# Crystal_Cmoy_Sch_EaglePCB_4.net
KiCad netlist of a schematic drawn in EAGLE
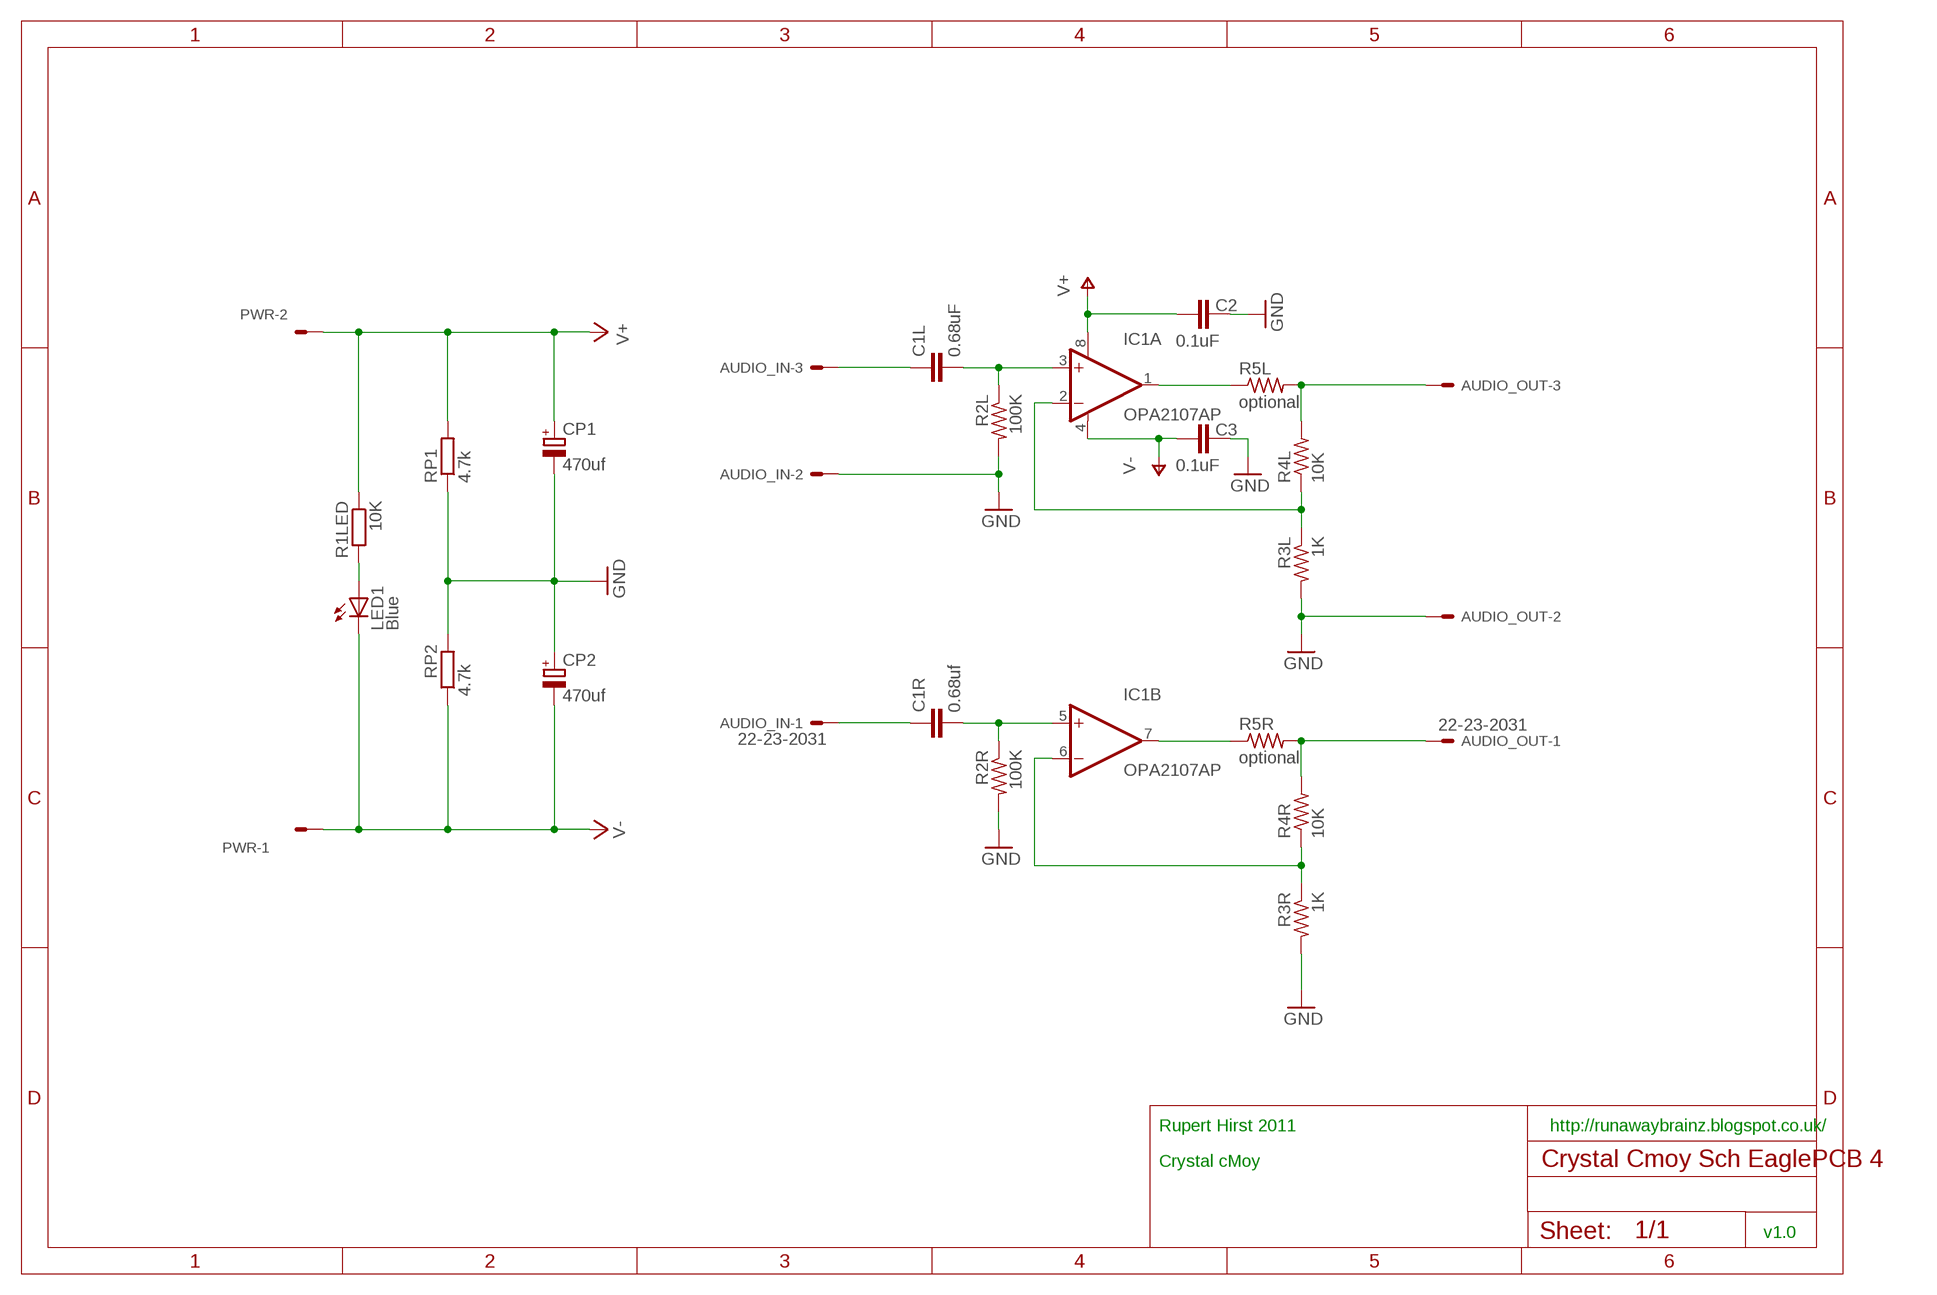
[diagram p0: schematic, sheet 1]

(export (version "E")
  (design (tool "Eeschema 10.0.6"))
  (components
    (comp (ref "AUDIO_IN")
      (value "22-23-2031")
      (footprint "eagle-import:22-23-2031")
      (libsource (lib "eagle-import") (part "22-23-2031"))
    )
    (comp (ref "AUDIO_OUT")
      (value "22-23-2031")
      (footprint "eagle-import:22-23-2031")
      (libsource (lib "eagle-import") (part "22-23-2031"))
    )
    (comp (ref "C1L")
      (value "0.68uF")
      (footprint "eagle-import:C15B7")
      (libsource (lib "eagle-import") (part "C15/7"))
    )
    (comp (ref "C1R")
      (value "0.68uf")
      (footprint "eagle-import:C15B7")
      (libsource (lib "eagle-import") (part "C15/7"))
    )
    (comp (ref "C2")
      (value "0.1uF")
      (footprint "eagle-import:C5B2.5")
      (libsource (lib "eagle-import") (part "C5/2.5"))
    )
    (comp (ref "C3")
      (value "0.1uF")
      (footprint "eagle-import:C5B5.5")
      (libsource (lib "eagle-import") (part "C5/5.5"))
    )
    (comp (ref "CP1")
      (value "470uf")
      (footprint "eagle-import:E5-13")
      (libsource (lib "eagle-import") (part "CPOL-EUE5-13"))
    )
    (comp (ref "CP2")
      (value "470uf")
      (footprint "eagle-import:E5-13")
      (libsource (lib "eagle-import") (part "CPOL-EUE5-13"))
    )
    (comp (ref "IC1")
      (value "OPA2107AP")
      (footprint "eagle-import:DIL08")
      (libsource (lib "eagle-import") (part "OPA2132P"))
    )
    (comp (ref "LED1")
      (value "Blue")
      (footprint "eagle-import:LED3MM")
      (libsource (lib "eagle-import") (part "LED3MM"))
    )
    (comp (ref "PWR")
      (value "22-23-2021")
      (footprint "eagle-import:22-23-2021")
      (libsource (lib "eagle-import") (part "22-23-2021"))
    )
    (comp (ref "R1LED")
      (value "10K")
      (footprint "eagle-import:0207_2V")
      (libsource (lib "eagle-import") (part "R-EU_0207/2V"))
    )
    (comp (ref "R2L")
      (value "100K")
      (footprint "eagle-import:0207_10")
      (libsource (lib "eagle-import") (part "R-US_0207/10"))
    )
    (comp (ref "R2R")
      (value "100K")
      (footprint "eagle-import:0207_10")
      (libsource (lib "eagle-import") (part "R-US_0207/10"))
    )
    (comp (ref "R3L")
      (value "1K")
      (footprint "eagle-import:0207_10")
      (libsource (lib "eagle-import") (part "R-US_0207/10"))
    )
    (comp (ref "R3R")
      (value "1K")
      (footprint "eagle-import:0207_10")
      (libsource (lib "eagle-import") (part "R-US_0207/10"))
    )
    (comp (ref "R4L")
      (value "10K")
      (footprint "eagle-import:0207_10")
      (libsource (lib "eagle-import") (part "R-US_0207/10"))
    )
    (comp (ref "R4R")
      (value "10K")
      (footprint "eagle-import:0207_10")
      (libsource (lib "eagle-import") (part "R-US_0207/10"))
    )
    (comp (ref "R5L")
      (value "optional")
      (footprint "eagle-import:0207_10")
      (libsource (lib "eagle-import") (part "R-US_0207/10"))
    )
    (comp (ref "R5R")
      (value "optional")
      (footprint "eagle-import:0207_10")
      (libsource (lib "eagle-import") (part "R-US_0207/10"))
    )
    (comp (ref "RP1")
      (value "4.7k")
      (footprint "eagle-import:0207_10")
      (libsource (lib "eagle-import") (part "R-EU_0207/10"))
    )
    (comp (ref "RP2")
      (value "4.7k")
      (footprint "eagle-import:0207_10")
      (libsource (lib "eagle-import") (part "R-EU_0207/10"))
    )
  )
  (nets
    (net (code "1") (name "GND") (class "Default")
      (node (ref "AUDIO_IN") (pin "2") (pinfunction "S_2") (pintype "passive"))
      (node (ref "AUDIO_OUT") (pin "2") (pinfunction "S_2") (pintype "passive"))
      (node (ref "C2") (pin "1") (pinfunction "1_1") (pintype "passive"))
      (node (ref "C3") (pin "2") (pinfunction "2_2") (pintype "passive"))
      (node (ref "CP1") (pin "-") (pinfunction "-_-") (pintype "passive"))
      (node (ref "CP2") (pin "+") (pinfunction "+_+") (pintype "passive"))
      (node (ref "R2L") (pin "2") (pinfunction "2_2") (pintype "passive"))
      (node (ref "R2R") (pin "2") (pinfunction "2_2") (pintype "passive"))
      (node (ref "R3L") (pin "2") (pinfunction "2_2") (pintype "passive"))
      (node (ref "R3R") (pin "2") (pinfunction "2_2") (pintype "passive"))
      (node (ref "RP1") (pin "1") (pinfunction "1_1") (pintype "passive"))
      (node (ref "RP2") (pin "2") (pinfunction "2_2") (pintype "passive"))
    )
    (net (code "2") (name "Net-(AUDIO_INA-S)") (class "Default")
      (node (ref "AUDIO_IN") (pin "1") (pinfunction "S_1") (pintype "passive"))
      (node (ref "C1R") (pin "1") (pinfunction "1_1") (pintype "passive"))
    )
    (net (code "3") (name "Net-(AUDIO_INC-S)") (class "Default")
      (node (ref "AUDIO_IN") (pin "3") (pinfunction "S_3") (pintype "passive"))
      (node (ref "C1L") (pin "1") (pinfunction "1_1") (pintype "passive"))
    )
    (net (code "4") (name "Net-(AUDIO_OUTA-S)") (class "Default")
      (node (ref "AUDIO_OUT") (pin "1") (pinfunction "S_1") (pintype "passive"))
      (node (ref "R4R") (pin "2") (pinfunction "2_2") (pintype "passive"))
      (node (ref "R5R") (pin "2") (pinfunction "2_2") (pintype "passive"))
    )
    (net (code "5") (name "Net-(AUDIO_OUTC-S)") (class "Default")
      (node (ref "AUDIO_OUT") (pin "3") (pinfunction "S_3") (pintype "passive"))
      (node (ref "R4L") (pin "2") (pinfunction "2_2") (pintype "passive"))
      (node (ref "R5L") (pin "2") (pinfunction "2_2") (pintype "passive"))
    )
    (net (code "6") (name "Net-(IC1A-+IN)") (class "Default")
      (node (ref "C1L") (pin "2") (pinfunction "2_2") (pintype "passive"))
      (node (ref "IC1") (pin "3") (pinfunction "+IN_3") (pintype "input"))
      (node (ref "R2L") (pin "1") (pinfunction "1_1") (pintype "passive"))
    )
    (net (code "7") (name "Net-(IC1A--IN)") (class "Default")
      (node (ref "IC1") (pin "2") (pinfunction "-IN_2") (pintype "input"))
      (node (ref "R3L") (pin "1") (pinfunction "1_1") (pintype "passive"))
      (node (ref "R4L") (pin "1") (pinfunction "1_1") (pintype "passive"))
    )
    (net (code "8") (name "Net-(IC1A-OUT)") (class "Default")
      (node (ref "IC1") (pin "1") (pinfunction "OUT_1") (pintype "output"))
      (node (ref "R5L") (pin "1") (pinfunction "1_1") (pintype "passive"))
    )
    (net (code "9") (name "Net-(IC1B-+IN)") (class "Default")
      (node (ref "C1R") (pin "2") (pinfunction "2_2") (pintype "passive"))
      (node (ref "IC1") (pin "5") (pinfunction "+IN_5") (pintype "input"))
      (node (ref "R2R") (pin "1") (pinfunction "1_1") (pintype "passive"))
    )
    (net (code "10") (name "Net-(IC1B--IN)") (class "Default")
      (node (ref "IC1") (pin "6") (pinfunction "-IN_6") (pintype "input"))
      (node (ref "R3R") (pin "1") (pinfunction "1_1") (pintype "passive"))
      (node (ref "R4R") (pin "1") (pinfunction "1_1") (pintype "passive"))
    )
    (net (code "11") (name "Net-(IC1B-OUT)") (class "Default")
      (node (ref "IC1") (pin "7") (pinfunction "OUT_7") (pintype "output"))
      (node (ref "R5R") (pin "1") (pinfunction "1_1") (pintype "passive"))
    )
    (net (code "12") (name "Net-(LED1-PadA)") (class "Default")
      (node (ref "LED1") (pin "A") (pinfunction "A_A") (pintype "passive"))
      (node (ref "R1LED") (pin "2") (pinfunction "2_2") (pintype "passive"))
    )
    (net (code "13") (name "V+") (class "Default")
      (node (ref "C2") (pin "2") (pinfunction "2_2") (pintype "passive"))
      (node (ref "CP1") (pin "+") (pinfunction "+_+") (pintype "passive"))
      (node (ref "IC1") (pin "8") (pinfunction "V+_8") (pintype "power_in"))
      (node (ref "PWR") (pin "2") (pinfunction "S_2") (pintype "passive"))
      (node (ref "R1LED") (pin "1") (pinfunction "1_1") (pintype "passive"))
      (node (ref "RP1") (pin "2") (pinfunction "2_2") (pintype "passive"))
    )
    (net (code "14") (name "V-") (class "Default")
      (node (ref "C3") (pin "1") (pinfunction "1_1") (pintype "passive"))
      (node (ref "CP2") (pin "-") (pinfunction "-_-") (pintype "passive"))
      (node (ref "IC1") (pin "4") (pinfunction "V-_4") (pintype "power_in"))
      (node (ref "LED1") (pin "K") (pinfunction "C_K") (pintype "passive"))
      (node (ref "PWR") (pin "1") (pinfunction "S_1") (pintype "passive"))
      (node (ref "RP2") (pin "1") (pinfunction "1_1") (pintype "passive"))
    )
  )
)
